# WiiCamBoard.net
KiCad netlist of a schematic drawn in EAGLE
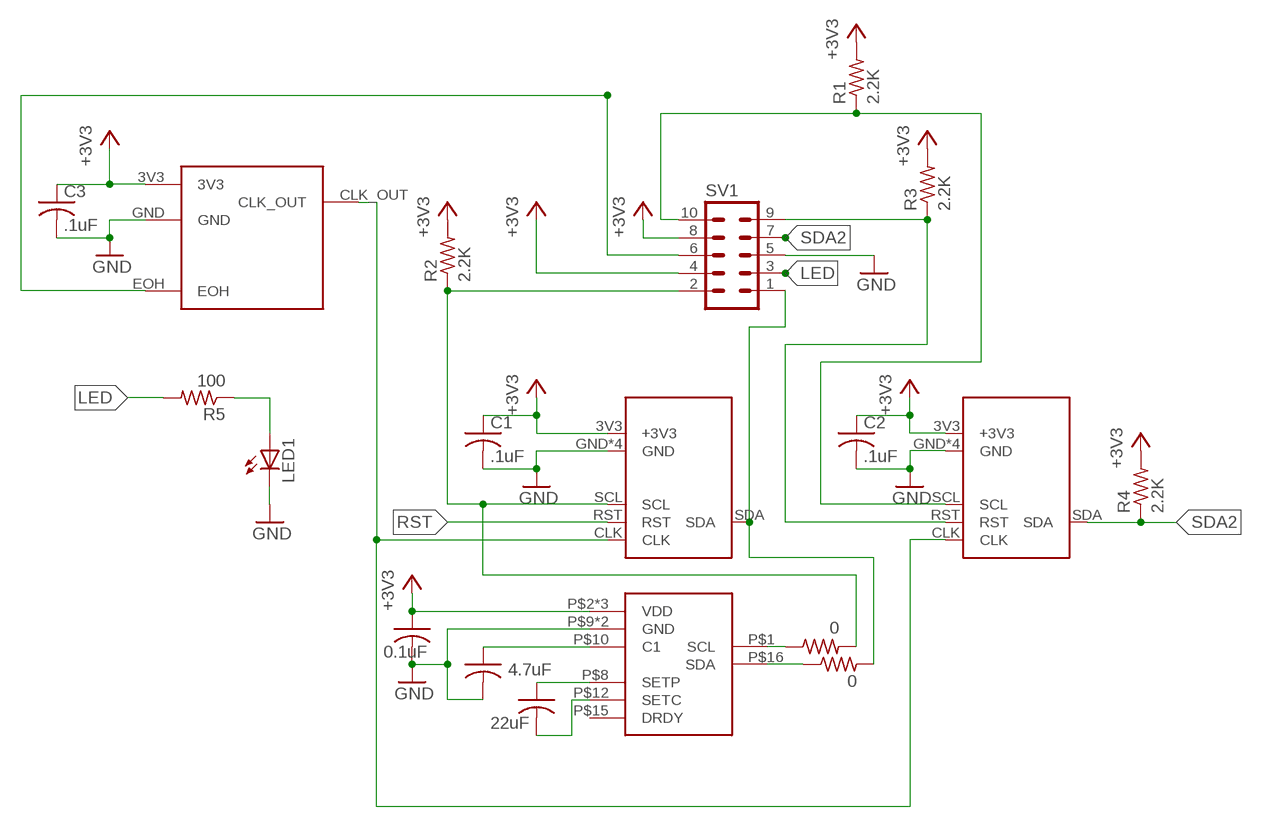
[diagram p0: schematic, sheet 1]

(export (version "E")
  (design (tool "Eeschema 10.0.6"))
  (components
    (comp (ref "C1")
      (value ".1uF")
      (footprint "eagle-import:C0805")
      (libsource (lib "eagle-import") (part "C-USC0805"))
    )
    (comp (ref "C2")
      (value ".1uF")
      (footprint "eagle-import:C0805")
      (libsource (lib "eagle-import") (part "C-USC0805"))
    )
    (comp (ref "C3")
      (value ".1uF")
      (footprint "eagle-import:C0805")
      (libsource (lib "eagle-import") (part "C-USC0805"))
    )
    (comp (ref "C4")
      (value "0.1uF")
      (footprint "eagle-import:C0805")
      (libsource (lib "eagle-import") (part "C-USC0805"))
    )
    (comp (ref "C5")
      (value "4.7uF")
      (footprint "eagle-import:C0805")
      (libsource (lib "eagle-import") (part "C-USC0805"))
    )
    (comp (ref "C6")
      (value "22uF")
      (footprint "eagle-import:C0805")
      (libsource (lib "eagle-import") (part "C-USC0805"))
    )
    (comp (ref "LED1")
      (value "LED5MM")
      (footprint "eagle-import:LED5MM")
      (libsource (lib "eagle-import") (part "LED5MM"))
    )
    (comp (ref "R1")
      (value "2.2K")
      (footprint "eagle-import:M0805")
      (libsource (lib "eagle-import") (part "resistor_R-US_M0805"))
    )
    (comp (ref "R2")
      (value "2.2K")
      (footprint "eagle-import:M0805")
      (libsource (lib "eagle-import") (part "resistor_R-US_M0805"))
    )
    (comp (ref "R3")
      (value "2.2K")
      (footprint "eagle-import:M0805")
      (libsource (lib "eagle-import") (part "resistor_R-US_M0805"))
    )
    (comp (ref "R4")
      (value "2.2K")
      (footprint "eagle-import:M0805")
      (libsource (lib "eagle-import") (part "resistor_R-US_M0805"))
    )
    (comp (ref "R5")
      (value "100")
      (footprint "eagle-import:M0805")
      (libsource (lib "eagle-import") (part "resistor_R-US_M0805"))
    )
    (comp (ref "R6")
      (value "0")
      (footprint "eagle-import:R0805")
      (libsource (lib "eagle-import") (part "R-US_R0805"))
    )
    (comp (ref "R7")
      (value "0")
      (footprint "eagle-import:R0805")
      (libsource (lib "eagle-import") (part "R-US_R0805"))
    )
    (comp (ref "SV1")
      (value "MA05-2")
      (footprint "eagle-import:MA05-2")
      (libsource (lib "eagle-import") (part "MA05-2"))
    )
    (comp (ref "U$1")
      (value "WII_IR_CAM")
      (footprint "eagle-import:WII_IR_CAM")
      (libsource (lib "eagle-import") (part "WII_IR_CAM"))
    )
    (comp (ref "U$2")
      (value "WII_IR_CAM")
      (footprint "eagle-import:WII_IR_CAM")
      (libsource (lib "eagle-import") (part "WII_IR_CAM"))
    )
    (comp (ref "U$3")
      (value "CB3LV-3C")
      (footprint "eagle-import:CB3LV-3C")
      (libsource (lib "eagle-import") (part "CB3LV-3C"))
    )
    (comp (ref "U$4")
      (value "HMC5883L")
      (footprint "eagle-import:HMC5883L")
      (libsource (lib "eagle-import") (part "HMC5883L"))
    )
  )
  (nets
    (net (code "1") (name "+3V3") (class "Default")
      (node (ref "C1") (pin "1") (pinfunction "1_1") (pintype "passive"))
      (node (ref "C2") (pin "1") (pinfunction "1_1") (pintype "passive"))
      (node (ref "C3") (pin "1") (pinfunction "1_1") (pintype "passive"))
      (node (ref "C4") (pin "1") (pinfunction "1_1") (pintype "passive"))
      (node (ref "R1") (pin "2") (pinfunction "2_2") (pintype "passive"))
      (node (ref "R2") (pin "2") (pinfunction "2_2") (pintype "passive"))
      (node (ref "R3") (pin "2") (pinfunction "2_2") (pintype "passive"))
      (node (ref "R4") (pin "2") (pinfunction "2_2") (pintype "passive"))
      (node (ref "SV1") (pin "4") (pinfunction "4_4") (pintype "passive"))
      (node (ref "SV1") (pin "8") (pinfunction "8_8") (pintype "passive"))
      (node (ref "U$1") (pin "3V3") (pinfunction "+3V3_3V3") (pintype "power_in"))
      (node (ref "U$2") (pin "3V3") (pinfunction "+3V3_3V3") (pintype "power_in"))
      (node (ref "U$3") (pin "3V3") (pinfunction "3V3_3V3") (pintype "power_in"))
      (node (ref "U$4") (pin "P$13") (pinfunction "VDD_P$13") (pintype "bidirectional"))
      (node (ref "U$4") (pin "P$2") (pinfunction "VDD_P$2") (pintype "bidirectional"))
      (node (ref "U$4") (pin "P$4") (pinfunction "VDD_P$4") (pintype "bidirectional"))
    )
    (net (code "2") (name "GND") (class "Default")
      (node (ref "C1") (pin "2") (pinfunction "2_2") (pintype "passive"))
      (node (ref "C2") (pin "2") (pinfunction "2_2") (pintype "passive"))
      (node (ref "C3") (pin "2") (pinfunction "2_2") (pintype "passive"))
      (node (ref "C4") (pin "2") (pinfunction "2_2") (pintype "passive"))
      (node (ref "C5") (pin "2") (pinfunction "2_2") (pintype "passive"))
      (node (ref "LED1") (pin "K") (pinfunction "C_K") (pintype "passive"))
      (node (ref "SV1") (pin "5") (pinfunction "5_5") (pintype "passive"))
      (node (ref "U$1") (pin "GND") (pinfunction "GND_GND") (pintype "power_in"))
      (node (ref "U$1") (pin "GND2") (pinfunction "GND_GND2") (pintype "power_in"))
      (node (ref "U$1") (pin "GND3") (pinfunction "GND_GND3") (pintype "power_in"))
      (node (ref "U$1") (pin "GND4") (pinfunction "GND_GND4") (pintype "power_in"))
      (node (ref "U$2") (pin "GND") (pinfunction "GND_GND") (pintype "power_in"))
      (node (ref "U$2") (pin "GND2") (pinfunction "GND_GND2") (pintype "power_in"))
      (node (ref "U$2") (pin "GND3") (pinfunction "GND_GND3") (pintype "power_in"))
      (node (ref "U$2") (pin "GND4") (pinfunction "GND_GND4") (pintype "power_in"))
      (node (ref "U$3") (pin "GND") (pinfunction "GND_GND") (pintype "power_in"))
      (node (ref "U$4") (pin "P$11") (pinfunction "GND_P$11") (pintype "bidirectional"))
      (node (ref "U$4") (pin "P$9") (pinfunction "GND_P$9") (pintype "bidirectional"))
    )
    (net (code "3") (name "LED") (class "Default")
      (node (ref "R5") (pin "2") (pinfunction "2_2") (pintype "passive"))
      (node (ref "SV1") (pin "3") (pinfunction "3_3") (pintype "passive"))
    )
    (net (code "4") (name "Net-(LED1-PadA)") (class "Default")
      (node (ref "LED1") (pin "A") (pinfunction "A_A") (pintype "passive"))
      (node (ref "R5") (pin "1") (pinfunction "1_1") (pintype "passive"))
    )
    (net (code "5") (name "Net-(R1-Pad1)") (class "Default")
      (node (ref "R1") (pin "1") (pinfunction "1_1") (pintype "passive"))
      (node (ref "SV1") (pin "10") (pinfunction "10_10") (pintype "passive"))
      (node (ref "U$2") (pin "SCL") (pinfunction "SCL_SCL") (pintype "bidirectional"))
    )
    (net (code "6") (name "Net-(R2-Pad1)") (class "Default")
      (node (ref "R2") (pin "1") (pinfunction "1_1") (pintype "passive"))
      (node (ref "R6") (pin "2") (pinfunction "2_2") (pintype "passive"))
      (node (ref "SV1") (pin "2") (pinfunction "2_2") (pintype "passive"))
      (node (ref "U$1") (pin "SCL") (pinfunction "SCL_SCL") (pintype "bidirectional"))
    )
    (net (code "7") (name "Net-(R7-Pad2)") (class "Default")
      (node (ref "R7") (pin "2") (pinfunction "2_2") (pintype "passive"))
      (node (ref "SV1") (pin "1") (pinfunction "1_1") (pintype "passive"))
      (node (ref "U$1") (pin "SDA") (pinfunction "SDA_SDA") (pintype "bidirectional"))
    )
    (net (code "8") (name "Net-(SV1-Pad6)") (class "Default")
      (node (ref "SV1") (pin "6") (pinfunction "6_6") (pintype "passive"))
      (node (ref "U$3") (pin "EOH") (pinfunction "EOH_EOH") (pintype "bidirectional"))
    )
    (net (code "9") (name "Net-(U$1-PadCLK)") (class "Default")
      (node (ref "U$1") (pin "CLK") (pinfunction "CLK_CLK") (pintype "bidirectional"))
      (node (ref "U$2") (pin "CLK") (pinfunction "CLK_CLK") (pintype "bidirectional"))
      (node (ref "U$3") (pin "CLK_OUT") (pinfunction "CLK_OUT_CLK_OUT") (pintype "bidirectional"))
    )
    (net (code "10") (name "Net-(U$4-C1)") (class "Default")
      (node (ref "C5") (pin "1") (pinfunction "1_1") (pintype "passive"))
      (node (ref "U$4") (pin "P$10") (pinfunction "C1_P$10") (pintype "bidirectional"))
    )
    (net (code "11") (name "Net-(U$4-SCL)") (class "Default")
      (node (ref "R6") (pin "1") (pinfunction "1_1") (pintype "passive"))
      (node (ref "U$4") (pin "P$1") (pinfunction "SCL_P$1") (pintype "bidirectional"))
    )
    (net (code "12") (name "Net-(U$4-SDA)") (class "Default")
      (node (ref "R7") (pin "1") (pinfunction "1_1") (pintype "passive"))
      (node (ref "U$4") (pin "P$16") (pinfunction "SDA_P$16") (pintype "bidirectional"))
    )
    (net (code "13") (name "Net-(U$4-SETC)") (class "Default")
      (node (ref "C6") (pin "2") (pinfunction "2_2") (pintype "passive"))
      (node (ref "U$4") (pin "P$12") (pinfunction "SETC_P$12") (pintype "bidirectional"))
    )
    (net (code "14") (name "Net-(U$4-SETP)") (class "Default")
      (node (ref "C6") (pin "1") (pinfunction "1_1") (pintype "passive"))
      (node (ref "U$4") (pin "P$8") (pinfunction "SETP_P$8") (pintype "bidirectional"))
    )
    (net (code "15") (name "RST") (class "Default")
      (node (ref "R3") (pin "1") (pinfunction "1_1") (pintype "passive"))
      (node (ref "SV1") (pin "9") (pinfunction "9_9") (pintype "passive"))
      (node (ref "U$1") (pin "RST") (pinfunction "RST_RST") (pintype "bidirectional"))
      (node (ref "U$2") (pin "RST") (pinfunction "RST_RST") (pintype "bidirectional"))
    )
    (net (code "16") (name "SDA2") (class "Default")
      (node (ref "R4") (pin "1") (pinfunction "1_1") (pintype "passive"))
      (node (ref "SV1") (pin "7") (pinfunction "7_7") (pintype "passive"))
      (node (ref "U$2") (pin "SDA") (pinfunction "SDA_SDA") (pintype "bidirectional"))
    )
    (net (code "17") (name "unconnected-(U$4-DRDY-PadP$15)") (class "Default")
      (node (ref "U$4") (pin "P$15") (pinfunction "DRDY_P$15") (pintype "bidirectional"))
    )
  )
)
